# AntiSpark_Switch.net
KiCad netlist of a schematic drawn in EAGLE
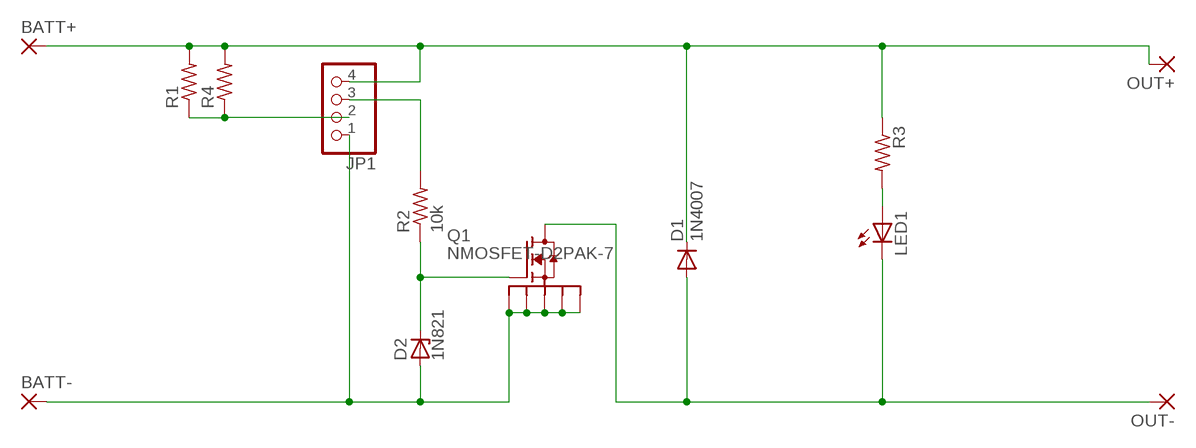
[diagram p0: schematic, sheet 1]

(export (version "E")
  (design (tool "Eeschema 10.0.6"))
  (components
    (comp (ref "BATT+")
      (value "WIREPAD4,16O1,6")
      (footprint "eagle-import:4,16O1,6")
      (libsource (lib "eagle-import") (part "WIREPAD4,16O1,6"))
    )
    (comp (ref "BATT-")
      (value "WIREPAD4,16O1,6")
      (footprint "eagle-import:4,16O1,6")
      (libsource (lib "eagle-import") (part "WIREPAD4,16O1,6"))
    )
    (comp (ref "D1")
      (value "1N4007")
      (footprint "eagle-import:DO41-10")
      (libsource (lib "eagle-import") (part "1N4004"))
    )
    (comp (ref "D2")
      (value "1N821")
      (footprint "eagle-import:DO35Z10")
      (libsource (lib "eagle-import") (part "1N821"))
    )
    (comp (ref "JP1")
      (value "PINHD-1X4")
      (footprint "eagle-import:1X04")
      (libsource (lib "eagle-import") (part "PINHD-1X4"))
    )
    (comp (ref "LED1")
      (value "LED5MM")
      (footprint "eagle-import:LED5MM")
      (libsource (lib "eagle-import") (part "LED5MM"))
    )
    (comp (ref "OUT+")
      (value "WIREPAD4,16O1,6")
      (footprint "eagle-import:4,16O1,6")
      (libsource (lib "eagle-import") (part "WIREPAD4,16O1,6"))
    )
    (comp (ref "OUT-")
      (value "WIREPAD4,16O1,6")
      (footprint "eagle-import:4,16O1,6")
      (libsource (lib "eagle-import") (part "WIREPAD4,16O1,6"))
    )
    (comp (ref "Q1")
      (value "NMOSFET-D2PAK-7")
      (footprint "eagle-import:D2PAK-7")
      (libsource (lib "eagle-import") (part "NMOSFET-D2PAK-7"))
    )
    (comp (ref "R1")
      (value "R-US_0207/7")
      (footprint "eagle-import:0207_7")
      (libsource (lib "eagle-import") (part "R-US_0207/7"))
    )
    (comp (ref "R2")
      (value "10k")
      (footprint "eagle-import:0207_7")
      (libsource (lib "eagle-import") (part "R-US_0207/7"))
    )
    (comp (ref "R3")
      (value "R-US_0207/7")
      (footprint "eagle-import:0207_7")
      (libsource (lib "eagle-import") (part "R-US_0207/7"))
    )
    (comp (ref "R4")
      (value "R-US_0207/7")
      (footprint "eagle-import:0207_7")
      (libsource (lib "eagle-import") (part "R-US_0207/7"))
    )
  )
  (nets
    (net (code "1") (name "Net-(BATT+-P)") (class "Default")
      (node (ref "BATT+") (pin "1") (pinfunction "P_1") (pintype "passive"))
      (node (ref "D1") (pin "C") (pinfunction "C_C") (pintype "passive"))
      (node (ref "JP1") (pin "4") (pinfunction "4_4") (pintype "passive"))
      (node (ref "OUT+") (pin "1") (pinfunction "P_1") (pintype "passive"))
      (node (ref "R1") (pin "2") (pinfunction "2_2") (pintype "passive"))
      (node (ref "R3") (pin "1") (pinfunction "1_1") (pintype "passive"))
      (node (ref "R4") (pin "2") (pinfunction "2_2") (pintype "passive"))
    )
    (net (code "2") (name "Net-(BATT--P)") (class "Default")
      (node (ref "BATT-") (pin "1") (pinfunction "P_1") (pintype "passive"))
      (node (ref "D2") (pin "A") (pinfunction "A_A") (pintype "passive"))
      (node (ref "JP1") (pin "1") (pinfunction "1_1") (pintype "passive"))
      (node (ref "Q1") (pin "S1") (pinfunction "S1_S1") (pintype "passive"))
      (node (ref "Q1") (pin "S2") (pinfunction "S2_S2") (pintype "passive"))
      (node (ref "Q1") (pin "S3") (pinfunction "S3_S3") (pintype "passive"))
      (node (ref "Q1") (pin "S4") (pinfunction "S4_S4") (pintype "passive"))
      (node (ref "Q1") (pin "S5") (pinfunction "S5_S5") (pintype "passive"))
    )
    (net (code "3") (name "Net-(D2-PadC)") (class "Default")
      (node (ref "D2") (pin "C") (pinfunction "C_C") (pintype "passive"))
      (node (ref "Q1") (pin "G") (pinfunction "G_G") (pintype "passive"))
      (node (ref "R2") (pin "1") (pinfunction "1_1") (pintype "passive"))
    )
    (net (code "4") (name "Net-(JP1-Pad2)") (class "Default")
      (node (ref "JP1") (pin "2") (pinfunction "2_2") (pintype "passive"))
      (node (ref "R1") (pin "1") (pinfunction "1_1") (pintype "passive"))
      (node (ref "R4") (pin "1") (pinfunction "1_1") (pintype "passive"))
    )
    (net (code "5") (name "Net-(JP1-Pad3)") (class "Default")
      (node (ref "JP1") (pin "3") (pinfunction "3_3") (pintype "passive"))
      (node (ref "R2") (pin "2") (pinfunction "2_2") (pintype "passive"))
    )
    (net (code "6") (name "Net-(LED1-C)") (class "Default")
      (node (ref "D1") (pin "A") (pinfunction "A_A") (pintype "passive"))
      (node (ref "LED1") (pin "K") (pinfunction "C_K") (pintype "passive"))
      (node (ref "OUT-") (pin "1") (pinfunction "P_1") (pintype "passive"))
      (node (ref "Q1") (pin "D") (pinfunction "D_D") (pintype "passive"))
    )
    (net (code "7") (name "Net-(LED1-PadA)") (class "Default")
      (node (ref "LED1") (pin "A") (pinfunction "A_A") (pintype "passive"))
      (node (ref "R3") (pin "2") (pinfunction "2_2") (pintype "passive"))
    )
  )
)
